# Power_Management.net
KiCad netlist of a schematic drawn in Altium Designer
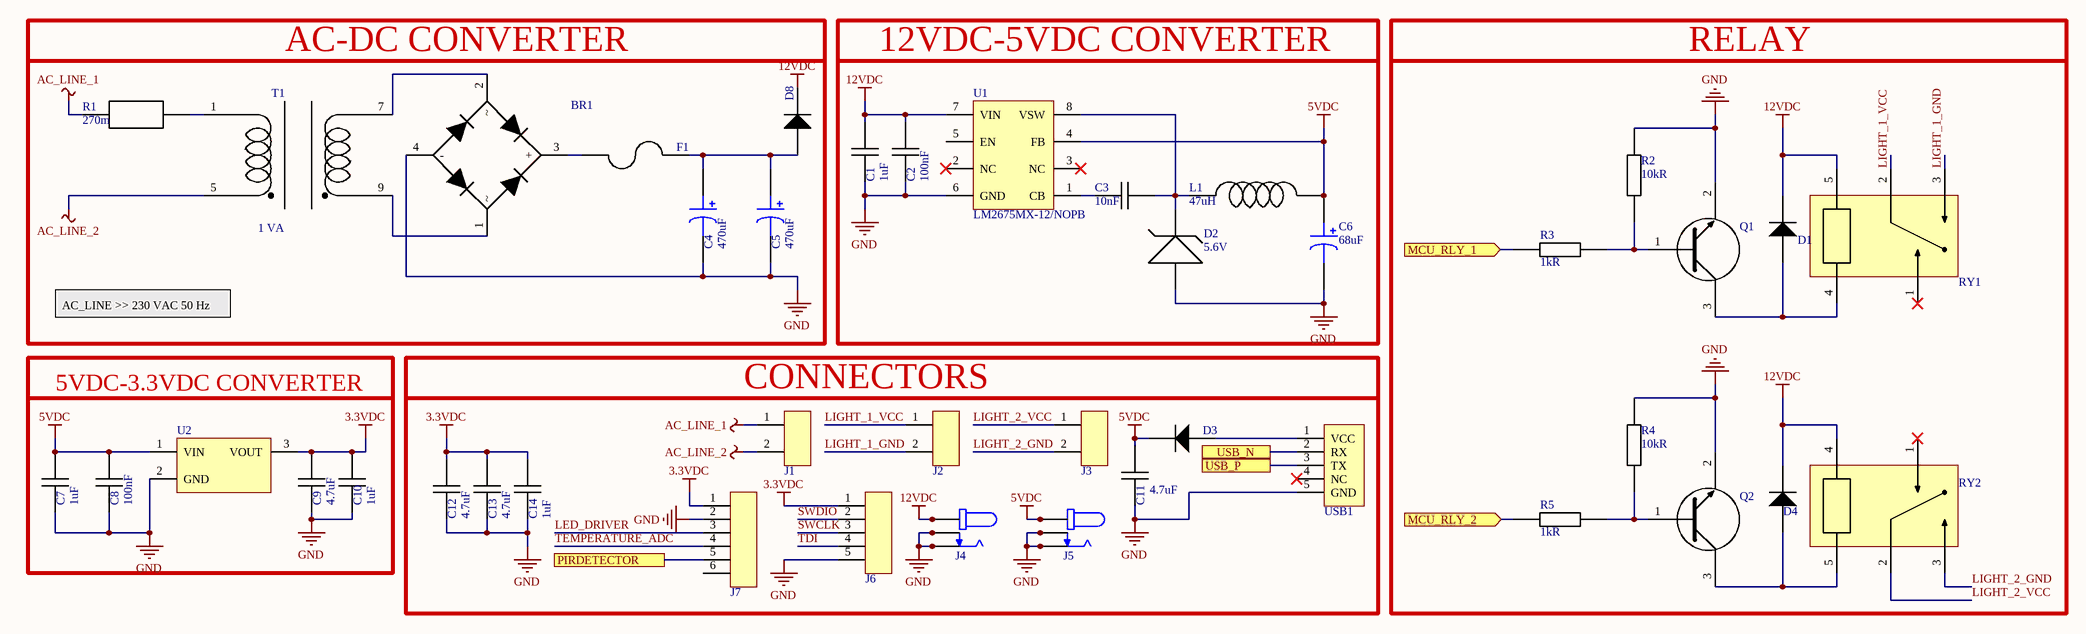
[diagram p0: Power Management.SchDoc]

(export (version "E")
  (design (tool "Eeschema 10.0.6"))
  (components
    (comp (ref "BR1")
      (value "DB105S")
      (footprint "DB105S")
      (description "Bridge Rectifier, DB-S, 1A, 600V, SMD Bridge")
      (fields (field (name "MANUFACTURER") "Sangdest Microelectronics") (field (name "DESIGNED BY") "FURKAN"))
      (libsource (lib "Udemy_Library") (part "DB105S"))
    )
    (comp (ref "C1")
      (value "1uF")
      (footprint "CAP_0805")
      (description "Multilayer Ceramic Capacitor, 1 uF, 50 V, 10%, X7R, 0805 [2012 Metric]")
      (fields
        (field (name "MANUFACTURER") "Samsung")
        (field (name "MANUFACTURER PART NUMBER") "CL21B105KBFNNNE")
        (field (name "DESIGNED BY") "FURKAN")
      )
      (libsource (lib "Udemy_Library") (part "CAP CER 1uF 0805"))
    )
    (comp (ref "C2")
      (value "100nF")
      (footprint "CAP_0603")
      (description "CAP CER 100 nF %20 0603 SMD")
      (fields
        (field (name "MANUFACTURER") "KEMET")
        (field (name "MANUFACTURER PART NUMBER") "C0603C104M5RACTU")
        (field (name "DESIGNED BY") "FURKAN")
      )
      (libsource (lib "Udemy_Library") (part "CAP CER 100nF 0603"))
    )
    (comp (ref "C3")
      (value "10nF")
      (footprint "CAP_0603")
      (description "CAP CER 10nF 10% 16V 0603 SMD")
      (fields
        (field (name "MANUFACTURER") "Walsin Technologies")
        (field (name "MANUFACTURER PART NUMBER") "0603B103K160CT")
        (field (name "DESIGNED BY") "FURKAN")
      )
      (libsource (lib "Udemy_Library") (part "CAP CER 10nF 0603"))
    )
    (comp (ref "C4")
      (value "ESH477M050AH4AA")
      (footprint "CAP_RADIAL_R10_P5")
      (description "Electrolytic capacitor, 470 µF, 50 V (DC), ±20 %, radial, pitch 5 mm, Ø 13 mm")
      (fields
        (field (name "MANUFACTURER") "KEMET")
        (field (name "CAPACITANCE") "470uF")
        (field (name "DESIGNED BY") "FURKAN")
      )
      (libsource (lib "Udemy_Library") (part "CAP ALU ELEC 470uF"))
    )
    (comp (ref "C5")
      (value "ESH477M050AH4AA")
      (footprint "CAP_RADIAL_R10_P5")
      (description "Electrolytic capacitor, 470 µF, 50 V (DC), ±20 %, radial, pitch 5 mm, Ø 13 mm")
      (fields
        (field (name "MANUFACTURER") "KEMET")
        (field (name "CAPACITANCE") "470uF")
        (field (name "DESIGNED BY") "FURKAN")
      )
      (libsource (lib "Udemy_Library") (part "CAP ALU ELEC 470uF"))
    )
    (comp (ref "C6")
      (value "EEV686M035A9HAA")
      (footprint "CAP_EEVSeries")
      (description "Cap Aluminum Lytic 68uF 35V 20%( 6.3 X 7.7mm) SMD 0.34 Ohm 280mA 2000h 105C T/R")
      (fields
        (field (name "MANUFACTURER") "KEMET")
        (field (name "CAPACITANCE") "68uF")
        (field (name "DESIGNED BY") "FURKAN")
      )
      (libsource (lib "Udemy_Library") (part "CAP ALU 68uF"))
    )
    (comp (ref "C7")
      (value "1uF")
      (footprint "CAP_0805")
      (description "Multilayer Ceramic Capacitor, 1 uF, 50 V, 10%, X7R, 0805 [2012 Metric]")
      (fields
        (field (name "MANUFACTURER") "Samsung")
        (field (name "MANUFACTURER PART NUMBER") "CL21B105KBFNNNE")
        (field (name "DESIGNED BY") "FURKAN")
      )
      (libsource (lib "Udemy_Library") (part "CAP CER 1uF 0805"))
    )
    (comp (ref "C8")
      (value "100nF")
      (footprint "CAP_0805")
      (description "CAP CER 100 nF 10% 50 V 0805 SMD")
      (fields
        (field (name "MANUFACTURER") "Samsung")
        (field (name "MANUFACTURER PART NUMBER") "CL21B104KBCNNNC")
        (field (name "DESIGNED BY") "FURKAN")
      )
      (libsource (lib "Udemy_Library") (part "CAP CER 100nF 0805"))
    )
    (comp (ref "C9")
      (value "4.7uF")
      (footprint "CAP_0805")
      (description "Multilayer Ceramic Capacitor, 4.7 uF, 25 V, ± 10%, X5R, 0805 [2012 Metric]")
      (fields
        (field (name "MANUFACTURER") "Samsung")
        (field (name "MANUFACTURER PART NUMBER") "CL21A475KAQNNNE")
        (field (name "DESIGNED BY") "FURKAN")
      )
      (libsource (lib "Udemy_Library") (part "CAP CER 4.7uF 0805"))
    )
    (comp (ref "C10")
      (value "1uF")
      (footprint "CAP_0805")
      (description "Multilayer Ceramic Capacitor, 1 uF, 50 V, 10%, X7R, 0805 [2012 Metric]")
      (fields
        (field (name "MANUFACTURER") "Samsung")
        (field (name "MANUFACTURER PART NUMBER") "CL21B105KBFNNNE")
        (field (name "DESIGNED BY") "FURKAN")
      )
      (libsource (lib "Udemy_Library") (part "CAP CER 1uF 0805"))
    )
    (comp (ref "C11")
      (value "4.7uF")
      (footprint "CAP_0805")
      (description "Multilayer Ceramic Capacitor, 4.7 uF, 25 V, ± 10%, X5R, 0805 [2012 Metric]")
      (fields
        (field (name "MANUFACTURER") "Samsung")
        (field (name "MANUFACTURER PART NUMBER") "CL21A475KAQNNNE")
        (field (name "DESIGNED BY") "FURKAN")
      )
      (libsource (lib "Udemy_Library") (part "CAP CER 4.7uF 0805"))
    )
    (comp (ref "C12")
      (value "4.7uF")
      (footprint "CAP_0805")
      (description "Multilayer Ceramic Capacitor, 4.7 uF, 25 V, ± 10%, X5R, 0805 [2012 Metric]")
      (fields
        (field (name "MANUFACTURER") "Samsung")
        (field (name "MANUFACTURER PART NUMBER") "CL21A475KAQNNNE")
        (field (name "DESIGNED BY") "FURKAN")
      )
      (libsource (lib "Udemy_Library") (part "CAP CER 4.7uF 0805"))
    )
    (comp (ref "C13")
      (value "4.7uF")
      (footprint "CAP_0805")
      (description "Multilayer Ceramic Capacitor, 4.7 uF, 25 V, ± 10%, X5R, 0805 [2012 Metric]")
      (fields
        (field (name "MANUFACTURER") "Samsung")
        (field (name "MANUFACTURER PART NUMBER") "CL21A475KAQNNNE")
        (field (name "DESIGNED BY") "FURKAN")
      )
      (libsource (lib "Udemy_Library") (part "CAP CER 4.7uF 0805"))
    )
    (comp (ref "C14")
      (value "1uF")
      (footprint "CAP_0805")
      (description "Multilayer Ceramic Capacitor, 1 uF, 50 V, 10%, X7R, 0805 [2012 Metric]")
      (fields
        (field (name "MANUFACTURER") "Samsung")
        (field (name "MANUFACTURER PART NUMBER") "CL21B105KBFNNNE")
        (field (name "DESIGNED BY") "FURKAN")
      )
      (libsource (lib "Udemy_Library") (part "CAP CER 1uF 0805"))
    )
    (comp (ref "D1")
      (value "1N4148WS")
      (footprint "SOD323F")
      (description "Diode Ultra Fast Recovery Rectifier 75V 0.15A 2-Pin SOD-323F T/R")
      (fields
        (field (name "MANUFACTURER") "ON Semiconductor / Fairchild")
        (field (name "DESIGNED BY") "FURKAN")
      )
      (libsource (lib "Udemy_Library") (part "1N4148WS"))
    )
    (comp (ref "D2")
      (value "1SMB5919BT3G")
      (footprint "SMB 403A")
      (description "Diode Zener Single 5.6V 5% 550mW Automotive 2-Pin SMB T/R")
      (fields
        (field (name "MANUFACTURER") "ON Semiconductor")
        (field (name "VOLTAGE RATING (DC)") "5.6V")
        (field (name "DESIGNED BY") "FURKAN")
      )
      (libsource (lib "Udemy_Library") (part "1SMB5919BT3G"))
    )
    (comp (ref "D3")
      (value "1N4148WS")
      (footprint "SOD323F")
      (description "Diode Ultra Fast Recovery Rectifier 75V 0.15A 2-Pin SOD-323F T/R")
      (fields
        (field (name "MANUFACTURER") "ON Semiconductor / Fairchild")
        (field (name "DESIGNED BY") "FURKAN")
      )
      (libsource (lib "Udemy_Library") (part "1N4148WS"))
    )
    (comp (ref "D4")
      (value "1N4148WS")
      (footprint "SOD323F")
      (description "Diode Ultra Fast Recovery Rectifier 75V 0.15A 2-Pin SOD-323F T/R")
      (fields
        (field (name "MANUFACTURER") "ON Semiconductor / Fairchild")
        (field (name "DESIGNED BY") "FURKAN")
      )
      (libsource (lib "Udemy_Library") (part "1N4148WS"))
    )
    (comp (ref "D8")
      (value "1N4148WS")
      (footprint "SOD323F")
      (description "Diode Ultra Fast Recovery Rectifier 75V 0.15A 2-Pin SOD-323F T/R")
      (fields
        (field (name "MANUFACTURER") "ON Semiconductor / Fairchild")
        (field (name "DESIGNED BY") "FURKAN")
      )
      (libsource (lib "Udemy_Library") (part "1N4148WS"))
    )
    (comp (ref "F1")
      (value "3413.0216.22")
      (footprint "FUSE_1206")
      (description "Fuse Chip Fast Acting 1A 32V SMD Solder Pad 1206 Glass T/R VDE/cULus")
      (fields (field (name "MANUFACTURER") "Schurter") (field (name "DESIGNED BY") "FURKAN"))
      (libsource (lib "Udemy_Library") (part "FUSE 3413.0216.22"))
    )
    (comp (ref "J1")
      (value "TBP01R1-508-02BE")
      (footprint "TBP01R1-508-02BE")
      (description "2~24 Poles, Pluggable, Receptacle, Horizontal, 5.08 Pitch, Terminal Block Connector")
      (fields (field (name "MANUFACTURER") "CUI Devices") (field (name "DESIGNED BY") "FURKAN"))
      (libsource (lib "Udemy_Library") (part "TBP01R1-508-02BE"))
    )
    (comp (ref "J2")
      (value "TBP01R1-508-02BE")
      (footprint "TBP01R1-508-02BE")
      (description "2~24 Poles, Pluggable, Receptacle, Horizontal, 5.08 Pitch, Terminal Block Connector")
      (fields (field (name "MANUFACTURER") "CUI Devices") (field (name "DESIGNED BY") "FURKAN"))
      (libsource (lib "Udemy_Library") (part "TBP01R1-508-02BE"))
    )
    (comp (ref "J3")
      (value "TBP01R1-508-02BE")
      (footprint "TBP01R1-508-02BE")
      (description "2~24 Poles, Pluggable, Receptacle, Horizontal, 5.08 Pitch, Terminal Block Connector")
      (fields (field (name "MANUFACTURER") "CUI Devices") (field (name "DESIGNED BY") "FURKAN"))
      (libsource (lib "Udemy_Library") (part "TBP01R1-508-02BE"))
    )
    (comp (ref "J4")
      (value "PJ-037AH-SMT-TR")
      (footprint "PJ-037AH-SMT-TR")
      (description "2.0 x 6.3 mm, 5.0 A, Horizontal, Surface Mount (SMT), Dc Power Jack Connector")
      (fields (field (name "MANUFACTURER") "CUI") (field (name "DESIGNED BY") "FURKAN"))
      (libsource (lib "Udemy_Library") (part "PJ-037AH-SMT-TR"))
    )
    (comp (ref "J5")
      (value "PJ-037AH-SMT-TR")
      (footprint "PJ-037AH-SMT-TR")
      (description "2.0 x 6.3 mm, 5.0 A, Horizontal, Surface Mount (SMT), Dc Power Jack Connector")
      (fields (field (name "MANUFACTURER") "CUI") (field (name "DESIGNED BY") "FURKAN"))
      (libsource (lib "Udemy_Library") (part "PJ-037AH-SMT-TR"))
    )
    (comp (ref "J6")
      (value "SMH-105-02-L-S")
      (footprint "PINHEADER1X5_RA")
      (description "PCB Receptacle, Board-to-Board, 2.54 mm, 1 Rows, 5 Contacts, Surface Mount, SMH")
      (fields (field (name "MANUFACTURER") "Samtec") (field (name "DESIGNED BY") "FURKAN"))
      (libsource (lib "Udemy_Library") (part "SMH-105-02-L-S"))
    )
    (comp (ref "J7")
      (value "64800611622")
      (footprint "64800611622")
      (description "WR-WTB Wire-to-Board Connectors 1.50 mm 6-Pin Connector")
      (fields (field (name "MANUFACTURER") "Wurth Electronics") (field (name "DESIGNED BY") "FURKAN"))
      (libsource (lib "Udemy_Library") (part "64800611622_Conn_6Pin"))
    )
    (comp (ref "L1")
      (value "47uH")
      (footprint "IND_1212")
      (description "Power Inductor, Aec-Q200, 47Uh, 0.39A Rohs Compliant: Yes ¦Wurth Elektronik 78438335470")
      (fields
        (field (name "MANUFACTURER") "Wurth Electronics")
        (field (name "MANUFACTURER PART NUMBER") "78438335470")
        (field (name "DESIGNED BY") "FURKAN")
      )
      (libsource (lib "Udemy_Library") (part "IND 47 uH"))
    )
    (comp (ref "Q1")
      (value "MMBT3904-7-F")
      (footprint "SOT23F")
      (description "Transistor General Purpose BJT NPN 40 Volt 0.2A Automotive 3-Pin SOT-23")
      (fields (field (name "MANUFACTURER") "Diodes Zetex") (field (name "DESIGNED BY") "FURKAN"))
      (libsource (lib "Udemy_Library") (part "MMBT3904-7-F"))
    )
    (comp (ref "Q2")
      (value "MMBT3904-7-F")
      (footprint "SOT23F")
      (description "Transistor General Purpose BJT NPN 40 Volt 0.2A Automotive 3-Pin SOT-23")
      (fields (field (name "MANUFACTURER") "Diodes Zetex") (field (name "DESIGNED BY") "FURKAN"))
      (libsource (lib "Udemy_Library") (part "MMBT3904-7-F"))
    )
    (comp (ref "R1")
      (value "5WD27")
      (footprint "5WD27")
      (description "Resistor 5 Watt Cermet Wirewound Flameproof .27 Ohm 5% Axial Lead")
      (fields
        (field (name "MANUFACTURER") "NTE Electronics")
        (field (name "TOLERANCE") "5%")
        (field (name "RESISTANCE") "270m")
        (field (name "DESIGNED BY") "FURKAN")
      )
      (libsource (lib "Udemy_Library") (part "5WD27"))
    )
    (comp (ref "R2")
      (value "10kR")
      (footprint "RES_0603")
      (description "RES 10K OHM %1 0603 SMD")
      (fields
        (field (name "MANUFACTURER") "Yageo")
        (field (name "MANUFACTURER PART NUMBER") "RC0603FR-0710KL")
        (field (name "DESIGNED BY") "FURKAN")
      )
      (libsource (lib "Udemy_Library") (part "RES 10K OHM 0603"))
    )
    (comp (ref "R3")
      (value "1kR")
      (footprint "RES_0603")
      (description "RES 1K OHM 1% 0603 SMD")
      (fields
        (field (name "MANUFACTURER") "Yageo")
        (field (name "MANUFACTURER PART NUMBER") "RC0603FR-071KL")
        (field (name "DESIGNED BY") "FURKAN")
      )
      (libsource (lib "Udemy_Library") (part "RES 1K OHM 0603"))
    )
    (comp (ref "R4")
      (value "10kR")
      (footprint "RES_0603")
      (description "RES 10K OHM %1 0603 SMD")
      (fields
        (field (name "MANUFACTURER") "Yageo")
        (field (name "MANUFACTURER PART NUMBER") "RC0603FR-0710KL")
        (field (name "DESIGNED BY") "FURKAN")
      )
      (libsource (lib "Udemy_Library") (part "RES 10K OHM 0603"))
    )
    (comp (ref "R5")
      (value "1kR")
      (footprint "RES_0603")
      (description "RES 1K OHM 1% 0603 SMD")
      (fields
        (field (name "MANUFACTURER") "Yageo")
        (field (name "MANUFACTURER PART NUMBER") "RC0603FR-071KL")
        (field (name "DESIGNED BY") "FURKAN")
      )
      (libsource (lib "Udemy_Library") (part "RES 1K OHM 0603"))
    )
    (comp (ref "RY1")
      (value "ALQ112")
      (footprint "ALQ112")
      (description "Electromechanical Relay 12VDC 360Ohm 10(NO)/3(NC)A SPDT (( 20mm 10mm 16mm)) THT Power Relay")
      (fields (field (name "MANUFACTURER") "Panasonic") (field (name "DESIGNED BY") "FURKAN"))
      (libsource (lib "Udemy_Library") (part "ALQ112"))
    )
    (comp (ref "RY2")
      (value "ALQ112")
      (footprint "ALQ112")
      (description "Electromechanical Relay 12VDC 360Ohm 10(NO)/3(NC)A SPDT (( 20mm 10mm 16mm)) THT Power Relay")
      (fields (field (name "MANUFACTURER") "Panasonic") (field (name "DESIGNED BY") "FURKAN"))
      (libsource (lib "") (part "ALQ112_1"))
    )
    (comp (ref "T1")
      (value "BV302S12010")
      (footprint "EI30")
      (description "Sealed Transformer EI30/10.5")
      (fields
        (field (name "MANUFACTURER") "Zettler Magnetics")
        (field (name "RATED POWER") "1 VA")
        (field (name "DESIGNED BY") "FURKAN")
      )
      (libsource (lib "Udemy_Library") (part "BV302S12010"))
    )
    (comp (ref "U1")
      (value "LM2675MX-12/NOPB")
      (footprint "SOIC8")
      (description "SIMPLE SWITCHER® 6.5V to 40V, 1A Low Component Count Step-Down Regulator 8-SOIC -40 to 125")
      (fields (field (name "MANUFACTURER") "TI National Semiconductor") (field (name "DESIGNED BY") "FURKAN"))
      (libsource (lib "Udemy_Library") (part "LM2675MX-12/NOPB"))
    )
    (comp (ref "U2")
      (value "AP7361-33E-13")
      (footprint "SOT223")
      (description "AP7361 Series 3.3 V 1 A Low SMT Dropout Fixed-Mode Regulator - SOT-223")
      (fields (field (name "MANUFACTURER") "Diodes") (field (name "DESIGNED BY") "FURKAN"))
      (libsource (lib "Udemy_Library") (part "AP7361-33E-13"))
    )
    (comp (ref "USB1")
      (value "10118192-0001LF")
      (footprint "MICRO_B_USB")
      (description "CONN USB MICRO B RECPT SMT R/A")
      (fields (field (name "MANUFACTURER") "Amphenol ICC / FCI") (field (name "DESIGNED BY") "FURKAN"))
      (libsource (lib "Udemy_Library") (part "Micro B USB Connector"))
    )
  )
  (nets
    (net (code "1") (name "/LED_DRIVER") (class "Default") (node (ref "J7") (pin "3") (pintype "passive")))
    (net (code "2") (name "/LIGHT_1_GND") (class "Default")
      (node (ref "J2") (pin "2") (pinfunction "2_2") (pintype "power_in"))
      (node (ref "RY1") (pin "3") (pinfunction "3_3") (pintype "passive"))
    )
    (net (code "3") (name "/LIGHT_1_VCC") (class "Default")
      (node (ref "J2") (pin "1") (pinfunction "1_1") (pintype "power_in"))
      (node (ref "RY1") (pin "2") (pinfunction "2_2") (pintype "passive"))
    )
    (net (code "4") (name "/LIGHT_2_GND") (class "Default")
      (node (ref "J3") (pin "2") (pinfunction "2_2") (pintype "power_in"))
      (node (ref "RY2") (pin "3") (pinfunction "3_3") (pintype "passive"))
    )
    (net (code "5") (name "/LIGHT_2_VCC") (class "Default")
      (node (ref "J3") (pin "1") (pinfunction "1_1") (pintype "power_in"))
      (node (ref "RY2") (pin "2") (pinfunction "2_2") (pintype "passive"))
    )
    (net (code "6") (name "/MCU_RLY_1") (class "Default")
      (node (ref "R3") (pin "1") (pinfunction "1_1") (pintype "passive"))
    )
    (net (code "7") (name "/MCU_RLY_2") (class "Default")
      (node (ref "R5") (pin "1") (pinfunction "1_1") (pintype "passive"))
    )
    (net (code "8") (name "/PIRDETECTOR") (class "Default") (node (ref "J7") (pin "5") (pintype "passive")))
    (net (code "9") (name "/SWCLK") (class "Default")
      (node (ref "J6") (pin "3") (pinfunction "3_3") (pintype "passive"))
    )
    (net (code "10") (name "/SWDIO") (class "Default")
      (node (ref "J6") (pin "2") (pinfunction "2_2") (pintype "passive"))
    )
    (net (code "11") (name "/TDI") (class "Default")
      (node (ref "J6") (pin "4") (pinfunction "4_4") (pintype "passive"))
    )
    (net (code "12") (name "/TEMPERATURE_ADC") (class "Default")
      (node (ref "J7") (pin "4") (pintype "passive"))
    )
    (net (code "13") (name "/USB_N") (class "Default")
      (node (ref "USB1") (pin "2") (pinfunction "RX_2") (pintype "passive"))
    )
    (net (code "14") (name "/USB_P") (class "Default")
      (node (ref "USB1") (pin "3") (pinfunction "TX_3") (pintype "passive"))
    )
    (net (code "15") (name "3.3VDC") (class "Default")
      (node (ref "C10") (pin "1") (pinfunction "1_1") (pintype "passive"))
      (node (ref "C12") (pin "2") (pinfunction "2_2") (pintype "passive"))
      (node (ref "C13") (pin "2") (pinfunction "2_2") (pintype "passive"))
      (node (ref "C14") (pin "2") (pinfunction "2_2") (pintype "passive"))
      (node (ref "C9") (pin "1") (pinfunction "1_1") (pintype "passive"))
      (node (ref "J6") (pin "1") (pinfunction "1_1") (pintype "passive"))
      (node (ref "J7") (pin "1") (pintype "passive"))
      (node (ref "U2") (pin "3") (pinfunction "VOUT_3") (pintype "passive"))
    )
    (net (code "16") (name "5VDC") (class "Default")
      (node (ref "C11") (pin "2") (pinfunction "2_2") (pintype "passive"))
      (node (ref "C6") (pin "1") (pinfunction "1_1") (pintype "passive"))
      (node (ref "C7") (pin "2") (pinfunction "2_2") (pintype "passive"))
      (node (ref "C8") (pin "2") (pinfunction "2_2") (pintype "passive"))
      (node (ref "D3") (pin "1") (pinfunction "1_1") (pintype "passive"))
      (node (ref "J5") (pin "1A") (pinfunction "1_1A") (pintype "power_in"))
      (node (ref "J5") (pin "1B") (pinfunction "VCC_1B") (pintype "power_in"))
      (node (ref "L1") (pin "2") (pinfunction "2_2") (pintype "passive"))
      (node (ref "U1") (pin "4") (pinfunction "FB_4") (pintype "passive"))
      (node (ref "U2") (pin "1") (pinfunction "VIN_1") (pintype "passive"))
    )
    (net (code "17") (name "12VDC") (class "Default")
      (node (ref "C1") (pin "2") (pinfunction "2_2") (pintype "passive"))
      (node (ref "C2") (pin "2") (pinfunction "2_2") (pintype "passive"))
      (node (ref "D1") (pin "1") (pinfunction "1_1") (pintype "passive"))
      (node (ref "D4") (pin "1") (pinfunction "1_1") (pintype "passive"))
      (node (ref "D8") (pin "1") (pinfunction "1_1") (pintype "passive"))
      (node (ref "J4") (pin "1A") (pinfunction "1_1A") (pintype "power_in"))
      (node (ref "J4") (pin "1B") (pinfunction "VCC_1B") (pintype "power_in"))
      (node (ref "RY1") (pin "5") (pinfunction "5_5") (pintype "passive"))
      (node (ref "RY2") (pin "4") (pinfunction "4_4") (pintype "passive"))
      (node (ref "U1") (pin "7") (pinfunction "VIN_7") (pintype "passive"))
    )
    (net (code "18") (name "AC_LINE_1") (class "Default")
      (node (ref "J1") (pin "1") (pinfunction "1_1") (pintype "power_in"))
      (node (ref "R1") (pin "1") (pinfunction "1_1") (pintype "passive"))
    )
    (net (code "19") (name "AC_LINE_2") (class "Default")
      (node (ref "J1") (pin "2") (pinfunction "2_2") (pintype "power_in"))
      (node (ref "T1") (pin "5") (pinfunction "5_5") (pintype "passive"))
    )
    (net (code "20") (name "GND") (class "Default")
      (node (ref "BR1") (pin "4") (pinfunction "-_4") (pintype "passive"))
      (node (ref "C1") (pin "1") (pinfunction "1_1") (pintype "passive"))
      (node (ref "C10") (pin "2") (pinfunction "2_2") (pintype "passive"))
      (node (ref "C11") (pin "1") (pinfunction "1_1") (pintype "passive"))
      (node (ref "C12") (pin "1") (pinfunction "1_1") (pintype "passive"))
      (node (ref "C13") (pin "1") (pinfunction "1_1") (pintype "passive"))
      (node (ref "C14") (pin "1") (pinfunction "1_1") (pintype "passive"))
      (node (ref "C2") (pin "1") (pinfunction "1_1") (pintype "passive"))
      (node (ref "C4") (pin "2") (pinfunction "2_2") (pintype "passive"))
      (node (ref "C5") (pin "2") (pinfunction "2_2") (pintype "passive"))
      (node (ref "C6") (pin "2") (pinfunction "2_2") (pintype "passive"))
      (node (ref "C7") (pin "1") (pinfunction "1_1") (pintype "passive"))
      (node (ref "C8") (pin "1") (pinfunction "1_1") (pintype "passive"))
      (node (ref "C9") (pin "2") (pinfunction "2_2") (pintype "passive"))
      (node (ref "D2") (pin "A") (pinfunction "A_A") (pintype "passive"))
      (node (ref "J4") (pin "2A") (pinfunction "2_2A") (pintype "power_in"))
      (node (ref "J4") (pin "2B") (pinfunction "GND_2B") (pintype "power_in"))
      (node (ref "J4") (pin "3A") (pinfunction "3_3A") (pintype "power_in"))
      (node (ref "J4") (pin "3B") (pinfunction "SH_3B") (pintype "power_in"))
      (node (ref "J5") (pin "2A") (pinfunction "2_2A") (pintype "power_in"))
      (node (ref "J5") (pin "2B") (pinfunction "GND_2B") (pintype "power_in"))
      (node (ref "J5") (pin "3A") (pinfunction "3_3A") (pintype "power_in"))
      (node (ref "J5") (pin "3B") (pinfunction "SH_3B") (pintype "power_in"))
      (node (ref "J6") (pin "5") (pinfunction "5_5") (pintype "passive"))
      (node (ref "J7") (pin "2") (pintype "passive"))
      (node (ref "Q1") (pin "2") (pinfunction "E_2") (pintype "passive"))
      (node (ref "Q2") (pin "2") (pinfunction "E_2") (pintype "passive"))
      (node (ref "R2") (pin "1") (pinfunction "1_1") (pintype "passive"))
      (node (ref "R4") (pin "1") (pinfunction "1_1") (pintype "passive"))
      (node (ref "U1") (pin "6") (pinfunction "GND_6") (pintype "passive"))
      (node (ref "U2") (pin "2") (pinfunction "GND_2") (pintype "passive"))
      (node (ref "USB1") (pin "5") (pinfunction "GND_5") (pintype "passive"))
    )
    (net (code "21") (name "Net-(BR1-+)") (class "Default")
      (node (ref "BR1") (pin "3") (pinfunction "+_3") (pintype "passive"))
      (node (ref "F1") (pin "1") (pinfunction "1_1") (pintype "passive"))
    )
    (net (code "22") (name "Net-(BR1-~-Pad1)") (class "Default")
      (node (ref "BR1") (pin "1") (pinfunction "~_1") (pintype "passive"))
      (node (ref "T1") (pin "9") (pinfunction "9_9") (pintype "passive"))
    )
    (net (code "23") (name "Net-(BR1-~-Pad2)") (class "Default")
      (node (ref "BR1") (pin "2") (pinfunction "~_2") (pintype "passive"))
      (node (ref "T1") (pin "7") (pinfunction "7_7") (pintype "passive"))
    )
    (net (code "24") (name "Net-(C4-Pad1)") (class "Default")
      (node (ref "C4") (pin "1") (pinfunction "1_1") (pintype "passive"))
      (node (ref "C5") (pin "1") (pinfunction "1_1") (pintype "passive"))
      (node (ref "D8") (pin "2") (pinfunction "2_2") (pintype "passive"))
      (node (ref "F1") (pin "2") (pinfunction "2_2") (pintype "passive"))
    )
    (net (code "25") (name "Net-(Q1-B)") (class "Default")
      (node (ref "Q1") (pin "1") (pinfunction "B_1") (pintype "passive"))
      (node (ref "R2") (pin "2") (pinfunction "2_2") (pintype "passive"))
      (node (ref "R3") (pin "2") (pinfunction "2_2") (pintype "passive"))
    )
    (net (code "26") (name "Net-(Q1-C)") (class "Default")
      (node (ref "D1") (pin "2") (pinfunction "2_2") (pintype "passive"))
      (node (ref "Q1") (pin "3") (pinfunction "C_3") (pintype "passive"))
      (node (ref "RY1") (pin "4") (pinfunction "4_4") (pintype "passive"))
    )
    (net (code "27") (name "Net-(Q2-B)") (class "Default")
      (node (ref "Q2") (pin "1") (pinfunction "B_1") (pintype "passive"))
      (node (ref "R4") (pin "2") (pinfunction "2_2") (pintype "passive"))
      (node (ref "R5") (pin "2") (pinfunction "2_2") (pintype "passive"))
    )
    (net (code "28") (name "Net-(Q2-C)") (class "Default")
      (node (ref "D4") (pin "2") (pinfunction "2_2") (pintype "passive"))
      (node (ref "Q2") (pin "3") (pinfunction "C_3") (pintype "passive"))
      (node (ref "RY2") (pin "5") (pinfunction "5_5") (pintype "passive"))
    )
    (net (code "29") (name "Net-(R1-Pad2)") (class "Default")
      (node (ref "R1") (pin "2") (pinfunction "2_2") (pintype "passive"))
      (node (ref "T1") (pin "1") (pinfunction "1_1") (pintype "passive"))
    )
    (net (code "30") (name "Net-(U1-CB)") (class "Default")
      (node (ref "C3") (pin "1") (pinfunction "1_1") (pintype "passive"))
      (node (ref "U1") (pin "1") (pinfunction "CB_1") (pintype "passive"))
    )
    (net (code "31") (name "Net-(U1-VSW)") (class "Default")
      (node (ref "C3") (pin "2") (pinfunction "2_2") (pintype "passive"))
      (node (ref "D2") (pin "C") (pinfunction "C_C") (pintype "passive"))
      (node (ref "L1") (pin "1") (pinfunction "1_1") (pintype "passive"))
      (node (ref "U1") (pin "8") (pinfunction "VSW_8") (pintype "passive"))
    )
    (net (code "32") (name "Net-(USB1-VCC)") (class "Default")
      (node (ref "D3") (pin "2") (pinfunction "2_2") (pintype "passive"))
      (node (ref "USB1") (pin "1") (pinfunction "VCC_1") (pintype "passive"))
    )
    (net (code "33") (name "unconnected-(J7-Pad6)") (class "Default")
      (node (ref "J7") (pin "6") (pintype "passive"))
    )
    (net (code "34") (name "unconnected-(RY1-Pad1)") (class "Default")
      (node (ref "RY1") (pin "1") (pinfunction "1_1") (pintype "passive+no_connect"))
    )
    (net (code "35") (name "unconnected-(RY2-Pad1)") (class "Default")
      (node (ref "RY2") (pin "1") (pinfunction "1_1") (pintype "passive+no_connect"))
    )
    (net (code "36") (name "unconnected-(U1-EN-Pad5)") (class "Default")
      (node (ref "U1") (pin "5") (pinfunction "EN_5") (pintype "passive"))
    )
    (net (code "37") (name "unconnected-(U1-NC-Pad2)") (class "Default")
      (node (ref "U1") (pin "2") (pinfunction "NC_2") (pintype "passive+no_connect"))
    )
    (net (code "38") (name "unconnected-(U1-NC-Pad3)") (class "Default")
      (node (ref "U1") (pin "3") (pinfunction "NC_3") (pintype "passive+no_connect"))
    )
    (net (code "39") (name "unconnected-(USB1-NC-Pad4)") (class "Default")
      (node (ref "USB1") (pin "4") (pinfunction "NC_4") (pintype "passive+no_connect"))
    )
  )
)
